# JTAG_connector2.net
KiCad netlist of a schematic drawn in Altium Designer
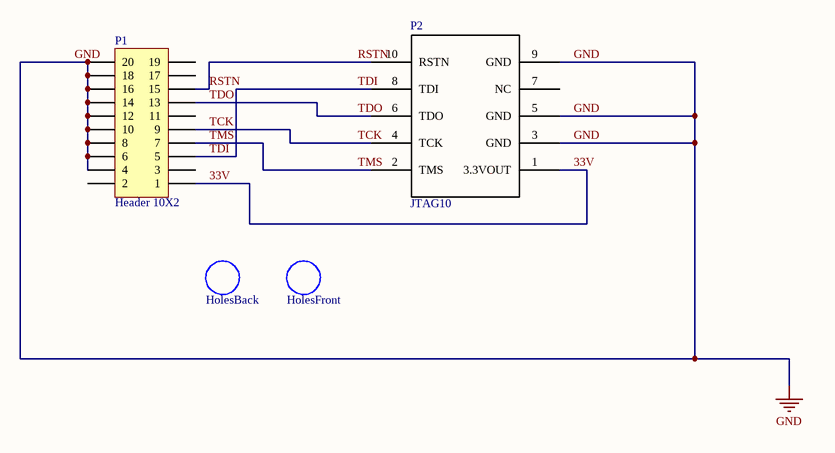
[diagram p0: JTAG_connector2.SchDoc]

(export (version "E")
  (design (tool "Eeschema 10.0.6"))
  (components
    (comp (ref "HolesBack")
      (value "non connect")
      (footprint "3/8\"Caster")
      (description "This is just a space saver to get the caster onto the pcb")
      (libsource (lib "mrone") (part "Caster"))
    )
    (comp (ref "HolesFront")
      (value "non connect")
      (footprint "3/8\"Caster")
      (description "This is just a space saver to get the caster onto the pcb")
      (libsource (lib "mrone") (part "Caster"))
    )
    (comp (ref "P1")
      (value "Header 10X2")
      (footprint "HDR2X10")
      (description "Header, 20-Pin, Dual row")
      (fields (field (name "PUBLISHER") "Altium Limited"))
      (libsource (lib "Miscellaneous Connectors") (part "Header 10X2"))
    )
    (comp (ref "P2") (value "JTAG10") (footprint "JTAG-10") (libsource (lib "mrone") (part "JTAG10")))
  )
  (nets
    (net (code "1") (name "/33V") (class "Default")
      (node (ref "P1") (pin "1") (pinfunction "1_1") (pintype "passive"))
      (node (ref "P2") (pin "1") (pinfunction "3.3VOUT_1") (pintype "passive"))
    )
    (net (code "2") (name "/RSTN") (class "Default")
      (node (ref "P1") (pin "15") (pinfunction "15_15") (pintype "passive"))
      (node (ref "P2") (pin "10") (pinfunction "RSTN_10") (pintype "passive"))
    )
    (net (code "3") (name "/TCK") (class "Default")
      (node (ref "P1") (pin "9") (pinfunction "9_9") (pintype "passive"))
      (node (ref "P2") (pin "4") (pinfunction "TCK_4") (pintype "passive"))
    )
    (net (code "4") (name "/TDI") (class "Default")
      (node (ref "P1") (pin "5") (pinfunction "5_5") (pintype "passive"))
      (node (ref "P2") (pin "8") (pinfunction "TDI_8") (pintype "passive"))
    )
    (net (code "5") (name "/TDO") (class "Default")
      (node (ref "P1") (pin "13") (pinfunction "13_13") (pintype "passive"))
      (node (ref "P2") (pin "6") (pinfunction "TDO_6") (pintype "passive"))
    )
    (net (code "6") (name "/TMS") (class "Default")
      (node (ref "P1") (pin "7") (pinfunction "7_7") (pintype "passive"))
      (node (ref "P2") (pin "2") (pinfunction "TMS_2") (pintype "passive"))
    )
    (net (code "7") (name "GND") (class "Default")
      (node (ref "P1") (pin "10") (pinfunction "10_10") (pintype "passive"))
      (node (ref "P1") (pin "12") (pinfunction "12_12") (pintype "passive"))
      (node (ref "P1") (pin "14") (pinfunction "14_14") (pintype "passive"))
      (node (ref "P1") (pin "16") (pinfunction "16_16") (pintype "passive"))
      (node (ref "P1") (pin "18") (pinfunction "18_18") (pintype "passive"))
      (node (ref "P1") (pin "20") (pinfunction "20_20") (pintype "passive"))
      (node (ref "P1") (pin "4") (pinfunction "4_4") (pintype "passive"))
      (node (ref "P1") (pin "6") (pinfunction "6_6") (pintype "passive"))
      (node (ref "P1") (pin "8") (pinfunction "8_8") (pintype "passive"))
      (node (ref "P2") (pin "3") (pinfunction "GND_3") (pintype "passive"))
      (node (ref "P2") (pin "5") (pinfunction "GND_5") (pintype "passive"))
      (node (ref "P2") (pin "9") (pinfunction "GND_9") (pintype "passive"))
    )
    (net (code "8") (name "unconnected-(P1-Pad2)") (class "Default")
      (node (ref "P1") (pin "2") (pinfunction "2_2") (pintype "passive"))
    )
    (net (code "9") (name "unconnected-(P1-Pad3)") (class "Default")
      (node (ref "P1") (pin "3") (pinfunction "3_3") (pintype "passive"))
    )
    (net (code "10") (name "unconnected-(P1-Pad11)") (class "Default")
      (node (ref "P1") (pin "11") (pinfunction "11_11") (pintype "passive"))
    )
    (net (code "11") (name "unconnected-(P1-Pad17)") (class "Default")
      (node (ref "P1") (pin "17") (pinfunction "17_17") (pintype "passive"))
    )
    (net (code "12") (name "unconnected-(P1-Pad19)") (class "Default")
      (node (ref "P1") (pin "19") (pinfunction "19_19") (pintype "passive"))
    )
    (net (code "13") (name "unconnected-(P2-NC-Pad7)") (class "Default")
      (node (ref "P2") (pin "7") (pinfunction "NC_7") (pintype "passive"))
    )
  )
)
